# CaravanPi_V4.net
KiCad netlist of a schematic drawn in EAGLE
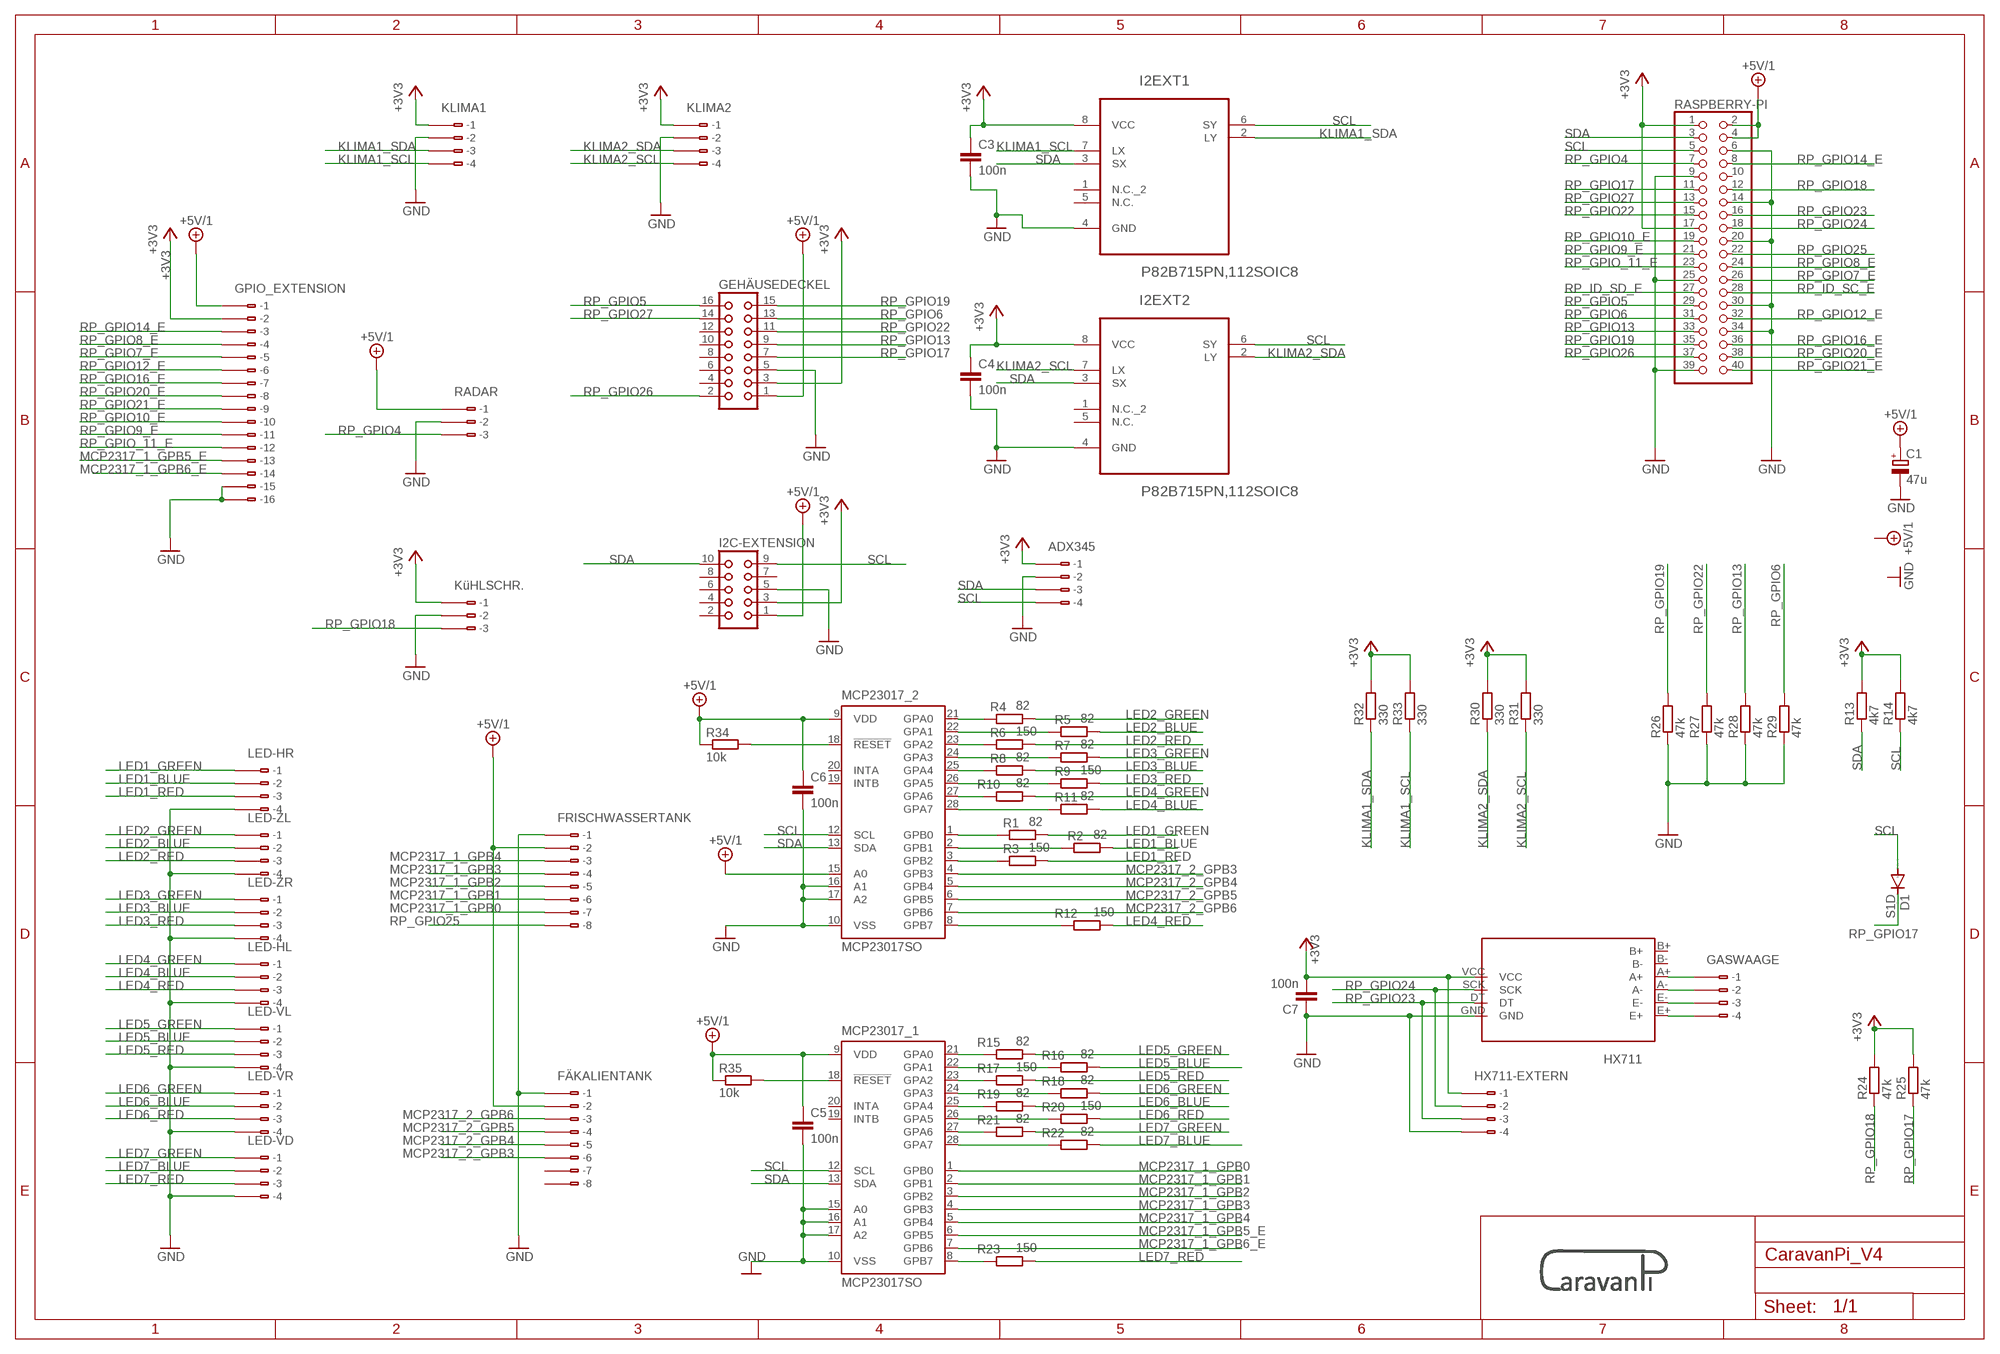
[diagram p0: schematic, sheet 1]

(export (version "E")
  (design (tool "Eeschema 10.0.6"))
  (components
    (comp (ref "ADX345")
      (value "233-404")
      (footprint "eagle-import:233-404")
      (libsource (lib "eagle-import") (part "233-404"))
    )
    (comp (ref "C1")
      (value "47u")
      (footprint "eagle-import:SMC_C")
      (libsource (lib "eagle-import") (part "CPOL-EUSMCC"))
    )
    (comp (ref "C3")
      (value "100n")
      (footprint "eagle-import:C1206")
      (libsource (lib "eagle-import") (part "C-EUC1206"))
    )
    (comp (ref "C4")
      (value "100n")
      (footprint "eagle-import:C1206")
      (libsource (lib "eagle-import") (part "C-EUC1206"))
    )
    (comp (ref "C5")
      (value "100n")
      (footprint "eagle-import:C1206")
      (libsource (lib "eagle-import") (part "C-EUC1206"))
    )
    (comp (ref "C6")
      (value "100n")
      (footprint "eagle-import:C1206")
      (libsource (lib "eagle-import") (part "C-EUC1206"))
    )
    (comp (ref "C7")
      (value "100n")
      (footprint "eagle-import:C1206")
      (libsource (lib "eagle-import") (part "C-EUC1206"))
    )
    (comp (ref "D1")
      (value "S1D")
      (footprint "eagle-import:DO214AC")
      (libsource (lib "eagle-import") (part "DIODE-DO214AC"))
    )
    (comp (ref "FRISCHWASSERTANK")
      (value "233-408")
      (footprint "eagle-import:233-408")
      (libsource (lib "eagle-import") (part "233-408"))
    )
    (comp (ref "FÄKALIENTANK")
      (value "233-408")
      (footprint "eagle-import:233-408")
      (libsource (lib "eagle-import") (part "233-408"))
    )
    (comp (ref "GASWAAGE")
      (value "233-404")
      (footprint "eagle-import:233-404")
      (libsource (lib "eagle-import") (part "233-404"))
    )
    (comp (ref "GEHÄUSEDECKEL")
      (value "CON16")
      (footprint "eagle-import:CON16")
      (libsource (lib "eagle-import") (part "CON16"))
    )
    (comp (ref "GPIO_EXTENSION")
      (value "233-516")
      (footprint "eagle-import:233-516")
      (fields (field (name "MF") "Wago Corporation") (field (name "MPN") "0233-0516"))
      (libsource (lib "eagle-import") (part "233-516"))
    )
    (comp (ref "HX711")
      (value "HX711A")
      (footprint "eagle-import:HX711")
      (libsource (lib "eagle-import") (part "HX711A"))
    )
    (comp (ref "HX711-EXTERN")
      (value "233-404")
      (footprint "eagle-import:233-404")
      (libsource (lib "eagle-import") (part "233-404"))
    )
    (comp (ref "I2C-EXTENSION")
      (value "CON10")
      (footprint "eagle-import:CON10")
      (libsource (lib "eagle-import") (part "CON10"))
    )
    (comp (ref "I2EXT1")
      (value "P82B715PN,112SOIC8")
      (footprint "eagle-import:SOP127P600X175-8N")
      (libsource (lib "eagle-import") (part "P82B715PN,112SOIC8"))
    )
    (comp (ref "I2EXT2")
      (value "P82B715PN,112SOIC8")
      (footprint "eagle-import:SOP127P600X175-8N")
      (libsource (lib "eagle-import") (part "P82B715PN,112SOIC8"))
    )
    (comp (ref "KLIMA1")
      (value "233-404")
      (footprint "eagle-import:233-404")
      (libsource (lib "eagle-import") (part "233-404"))
    )
    (comp (ref "KLIMA2")
      (value "233-404")
      (footprint "eagle-import:233-404")
      (libsource (lib "eagle-import") (part "233-404"))
    )
    (comp (ref "KüHLSCHR.")
      (value "233-403")
      (footprint "eagle-import:233-403")
      (libsource (lib "eagle-import") (part "233-403"))
    )
    (comp (ref "LED-HL")
      (value "233-504")
      (footprint "eagle-import:233-504")
      (fields (field (name "MF") "Wago Corporation") (field (name "MPN") "0233-0504"))
      (libsource (lib "eagle-import") (part "233-504"))
    )
    (comp (ref "LED-HR")
      (value "233-504")
      (footprint "eagle-import:233-504")
      (fields (field (name "MF") "Wago Corporation") (field (name "MPN") "0233-0504"))
      (libsource (lib "eagle-import") (part "233-504"))
    )
    (comp (ref "LED-VD")
      (value "233-504")
      (footprint "eagle-import:233-504")
      (fields (field (name "MF") "Wago Corporation") (field (name "MPN") "0233-0504"))
      (libsource (lib "eagle-import") (part "233-504"))
    )
    (comp (ref "LED-VL")
      (value "233-504")
      (footprint "eagle-import:233-504")
      (fields (field (name "MF") "Wago Corporation") (field (name "MPN") "0233-0504"))
      (libsource (lib "eagle-import") (part "233-504"))
    )
    (comp (ref "LED-VR")
      (value "233-504")
      (footprint "eagle-import:233-504")
      (fields (field (name "MF") "Wago Corporation") (field (name "MPN") "0233-0504"))
      (libsource (lib "eagle-import") (part "233-504"))
    )
    (comp (ref "LED-ZL")
      (value "233-504")
      (footprint "eagle-import:233-504")
      (fields (field (name "MF") "Wago Corporation") (field (name "MPN") "0233-0504"))
      (libsource (lib "eagle-import") (part "233-504"))
    )
    (comp (ref "LED-ZR")
      (value "233-504")
      (footprint "eagle-import:233-504")
      (fields (field (name "MF") "Wago Corporation") (field (name "MPN") "0233-0504"))
      (libsource (lib "eagle-import") (part "233-504"))
    )
    (comp (ref "MCP23017_1")
      (value "MCP23017SO")
      (footprint "eagle-import:SO28W")
      (libsource (lib "eagle-import") (part "MCP23017SO"))
    )
    (comp (ref "MCP23017_2")
      (value "MCP23017SO")
      (footprint "eagle-import:SO28W")
      (libsource (lib "eagle-import") (part "MCP23017SO"))
    )
    (comp (ref "R1")
      (value "82")
      (footprint "eagle-import:M1206")
      (libsource (lib "eagle-import") (part "R-EU_M1206"))
    )
    (comp (ref "R2")
      (value "82")
      (footprint "eagle-import:M1206")
      (libsource (lib "eagle-import") (part "R-EU_M1206"))
    )
    (comp (ref "R3")
      (value "150")
      (footprint "eagle-import:M1206")
      (libsource (lib "eagle-import") (part "R-EU_M1206"))
    )
    (comp (ref "R4")
      (value "82")
      (footprint "eagle-import:M1206")
      (libsource (lib "eagle-import") (part "R-EU_M1206"))
    )
    (comp (ref "R5")
      (value "82")
      (footprint "eagle-import:M1206")
      (libsource (lib "eagle-import") (part "R-EU_M1206"))
    )
    (comp (ref "R6")
      (value "150")
      (footprint "eagle-import:M1206")
      (libsource (lib "eagle-import") (part "R-EU_M1206"))
    )
    (comp (ref "R7")
      (value "82")
      (footprint "eagle-import:M1206")
      (libsource (lib "eagle-import") (part "R-EU_M1206"))
    )
    (comp (ref "R8")
      (value "82")
      (footprint "eagle-import:M1206")
      (libsource (lib "eagle-import") (part "R-EU_M1206"))
    )
    (comp (ref "R9")
      (value "150")
      (footprint "eagle-import:M1206")
      (libsource (lib "eagle-import") (part "R-EU_M1206"))
    )
    (comp (ref "R10")
      (value "82")
      (footprint "eagle-import:M1206")
      (libsource (lib "eagle-import") (part "R-EU_M1206"))
    )
    (comp (ref "R11")
      (value "82")
      (footprint "eagle-import:M1206")
      (libsource (lib "eagle-import") (part "R-EU_M1206"))
    )
    (comp (ref "R12")
      (value "150")
      (footprint "eagle-import:M1206")
      (libsource (lib "eagle-import") (part "R-EU_M1206"))
    )
    (comp (ref "R13")
      (value "4k7")
      (footprint "eagle-import:M1206")
      (libsource (lib "eagle-import") (part "R-EU_M1206"))
    )
    (comp (ref "R14")
      (value "4k7")
      (footprint "eagle-import:M1206")
      (libsource (lib "eagle-import") (part "R-EU_M1206"))
    )
    (comp (ref "R15")
      (value "82")
      (footprint "eagle-import:M1206")
      (libsource (lib "eagle-import") (part "R-EU_M1206"))
    )
    (comp (ref "R16")
      (value "82")
      (footprint "eagle-import:M1206")
      (libsource (lib "eagle-import") (part "R-EU_M1206"))
    )
    (comp (ref "R17")
      (value "150")
      (footprint "eagle-import:M1206")
      (libsource (lib "eagle-import") (part "R-EU_M1206"))
    )
    (comp (ref "R18")
      (value "82")
      (footprint "eagle-import:M1206")
      (libsource (lib "eagle-import") (part "R-EU_M1206"))
    )
    (comp (ref "R19")
      (value "82")
      (footprint "eagle-import:M1206")
      (libsource (lib "eagle-import") (part "R-EU_M1206"))
    )
    (comp (ref "R20")
      (value "150")
      (footprint "eagle-import:M1206")
      (libsource (lib "eagle-import") (part "R-EU_M1206"))
    )
    (comp (ref "R21")
      (value "82")
      (footprint "eagle-import:M1206")
      (libsource (lib "eagle-import") (part "R-EU_M1206"))
    )
    (comp (ref "R22")
      (value "82")
      (footprint "eagle-import:M1206")
      (libsource (lib "eagle-import") (part "R-EU_M1206"))
    )
    (comp (ref "R23")
      (value "150")
      (footprint "eagle-import:M1206")
      (libsource (lib "eagle-import") (part "R-EU_M1206"))
    )
    (comp (ref "R24")
      (value "47k")
      (footprint "eagle-import:M1206")
      (libsource (lib "eagle-import") (part "R-EU_M1206"))
    )
    (comp (ref "R25")
      (value "47k")
      (footprint "eagle-import:M1206")
      (libsource (lib "eagle-import") (part "R-EU_M1206"))
    )
    (comp (ref "R26")
      (value "47k")
      (footprint "eagle-import:M1206")
      (libsource (lib "eagle-import") (part "R-EU_M1206"))
    )
    (comp (ref "R27")
      (value "47k")
      (footprint "eagle-import:M1206")
      (libsource (lib "eagle-import") (part "R-EU_M1206"))
    )
    (comp (ref "R28")
      (value "47k")
      (footprint "eagle-import:M1206")
      (libsource (lib "eagle-import") (part "R-EU_M1206"))
    )
    (comp (ref "R29")
      (value "47k")
      (footprint "eagle-import:M1206")
      (libsource (lib "eagle-import") (part "R-EU_M1206"))
    )
    (comp (ref "R30")
      (value "330")
      (footprint "eagle-import:M1206")
      (libsource (lib "eagle-import") (part "R-EU_M1206"))
    )
    (comp (ref "R31")
      (value "330")
      (footprint "eagle-import:M1206")
      (libsource (lib "eagle-import") (part "R-EU_M1206"))
    )
    (comp (ref "R32")
      (value "330")
      (footprint "eagle-import:M1206")
      (libsource (lib "eagle-import") (part "R-EU_M1206"))
    )
    (comp (ref "R33")
      (value "330")
      (footprint "eagle-import:M1206")
      (libsource (lib "eagle-import") (part "R-EU_M1206"))
    )
    (comp (ref "R34")
      (value "10k")
      (footprint "eagle-import:M1206")
      (libsource (lib "eagle-import") (part "R-EU_M1206"))
    )
    (comp (ref "R35")
      (value "10k")
      (footprint "eagle-import:M1206")
      (libsource (lib "eagle-import") (part "R-EU_M1206"))
    )
    (comp (ref "RADAR")
      (value "233-403")
      (footprint "eagle-import:233-403")
      (libsource (lib "eagle-import") (part "233-403"))
    )
    (comp (ref "RASPBERRY-PI")
      (value "PINHD-2X20")
      (footprint "eagle-import:2X20")
      (libsource (lib "eagle-import") (part "PINHD-2X20"))
    )
    (comp (ref "U$1")
      (value "CARAVAN_PI_LOGO")
      (footprint "eagle-import:CARAVAN_PI_LOGO")
      (libsource (lib "eagle-import") (part "CARAVAN_PI_LOGO"))
    )
  )
  (nets
    (net (code "1") (name "+3V3") (class "Default")
      (node (ref "ADX345") (pin "B1") (pinfunction "B-1_B1") (pintype "passive"))
      (node (ref "C3") (pin "1") (pinfunction "1_1") (pintype "passive"))
      (node (ref "C4") (pin "1") (pinfunction "1_1") (pintype "passive"))
      (node (ref "C7") (pin "2") (pinfunction "2_2") (pintype "passive"))
      (node (ref "GEHÄUSEDECKEL") (pin "3") (pinfunction "3_3") (pintype "passive"))
      (node (ref "GPIO_EXTENSION") (pin "B2") (pinfunction "B-2_B2") (pintype "passive"))
      (node (ref "HX711") (pin "VCC") (pinfunction "VCC_VCC") (pintype "bidirectional"))
      (node (ref "HX711-EXTERN") (pin "B1") (pinfunction "B-1_B1") (pintype "passive"))
      (node (ref "I2C-EXTENSION") (pin "3") (pinfunction "3_3") (pintype "passive"))
      (node (ref "I2EXT1") (pin "8") (pinfunction "VCC_8") (pintype "power_in"))
      (node (ref "I2EXT2") (pin "8") (pinfunction "VCC_8") (pintype "power_in"))
      (node (ref "KLIMA1") (pin "B1") (pinfunction "B-1_B1") (pintype "passive"))
      (node (ref "KLIMA2") (pin "B1") (pinfunction "B-1_B1") (pintype "passive"))
      (node (ref "KüHLSCHR.") (pin "B1") (pinfunction "B-1_B1") (pintype "passive"))
      (node (ref "R13") (pin "2") (pinfunction "2_2") (pintype "passive"))
      (node (ref "R14") (pin "2") (pinfunction "2_2") (pintype "passive"))
      (node (ref "R24") (pin "2") (pinfunction "2_2") (pintype "passive"))
      (node (ref "R25") (pin "2") (pinfunction "2_2") (pintype "passive"))
      (node (ref "R30") (pin "2") (pinfunction "2_2") (pintype "passive"))
      (node (ref "R31") (pin "2") (pinfunction "2_2") (pintype "passive"))
      (node (ref "R32") (pin "2") (pinfunction "2_2") (pintype "passive"))
      (node (ref "R33") (pin "2") (pinfunction "2_2") (pintype "passive"))
      (node (ref "RASPBERRY-PI") (pin "1") (pinfunction "1_1") (pintype "passive"))
      (node (ref "RASPBERRY-PI") (pin "17") (pinfunction "17_17") (pintype "passive"))
    )
    (net (code "2") (name "+5V{slash}1") (class "Default")
      (node (ref "C1") (pin "+") (pinfunction "+_+") (pintype "passive"))
      (node (ref "C5") (pin "1") (pinfunction "1_1") (pintype "passive"))
      (node (ref "C6") (pin "1") (pinfunction "1_1") (pintype "passive"))
      (node (ref "FRISCHWASSERTANK") (pin "B2") (pinfunction "B-2_B2") (pintype "passive"))
      (node (ref "FÄKALIENTANK") (pin "B2") (pinfunction "B-2_B2") (pintype "passive"))
      (node (ref "GEHÄUSEDECKEL") (pin "1") (pinfunction "1_1") (pintype "passive"))
      (node (ref "GPIO_EXTENSION") (pin "B1") (pinfunction "B-1_B1") (pintype "passive"))
      (node (ref "I2C-EXTENSION") (pin "1") (pinfunction "1_1") (pintype "passive"))
      (node (ref "MCP23017_1") (pin "9") (pinfunction "VDD_9") (pintype "power_in"))
      (node (ref "MCP23017_2") (pin "15") (pinfunction "A0_15") (pintype "input"))
      (node (ref "MCP23017_2") (pin "9") (pinfunction "VDD_9") (pintype "power_in"))
      (node (ref "R34") (pin "1") (pinfunction "1_1") (pintype "passive"))
      (node (ref "R35") (pin "1") (pinfunction "1_1") (pintype "passive"))
      (node (ref "RADAR") (pin "B1") (pinfunction "B-1_B1") (pintype "passive"))
      (node (ref "RASPBERRY-PI") (pin "2") (pinfunction "2_2") (pintype "passive"))
      (node (ref "RASPBERRY-PI") (pin "4") (pinfunction "4_4") (pintype "passive"))
    )
    (net (code "3") (name "/KLIMA1_SCL") (class "Default")
      (node (ref "I2EXT1") (pin "7") (pinfunction "LX_7") (pintype "bidirectional"))
      (node (ref "KLIMA1") (pin "B4") (pinfunction "B-4_B4") (pintype "passive"))
      (node (ref "R33") (pin "1") (pinfunction "1_1") (pintype "passive"))
    )
    (net (code "4") (name "/KLIMA1_SDA") (class "Default")
      (node (ref "I2EXT1") (pin "2") (pinfunction "LY_2") (pintype "bidirectional"))
      (node (ref "KLIMA1") (pin "B3") (pinfunction "B-3_B3") (pintype "passive"))
      (node (ref "R32") (pin "1") (pinfunction "1_1") (pintype "passive"))
    )
    (net (code "5") (name "/KLIMA2_SCL") (class "Default")
      (node (ref "I2EXT2") (pin "7") (pinfunction "LX_7") (pintype "bidirectional"))
      (node (ref "KLIMA2") (pin "B4") (pinfunction "B-4_B4") (pintype "passive"))
      (node (ref "R31") (pin "1") (pinfunction "1_1") (pintype "passive"))
    )
    (net (code "6") (name "/KLIMA2_SDA") (class "Default")
      (node (ref "I2EXT2") (pin "2") (pinfunction "LY_2") (pintype "bidirectional"))
      (node (ref "KLIMA2") (pin "B3") (pinfunction "B-3_B3") (pintype "passive"))
      (node (ref "R30") (pin "1") (pinfunction "1_1") (pintype "passive"))
    )
    (net (code "7") (name "/LED1_BLUE") (class "Default")
      (node (ref "LED-HR") (pin "B2") (pinfunction "B-2_B2") (pintype "passive"))
      (node (ref "R2") (pin "2") (pinfunction "2_2") (pintype "passive"))
    )
    (net (code "8") (name "/LED1_GREEN") (class "Default")
      (node (ref "LED-HR") (pin "B1") (pinfunction "B-1_B1") (pintype "passive"))
      (node (ref "R1") (pin "2") (pinfunction "2_2") (pintype "passive"))
    )
    (net (code "9") (name "/LED1_RED") (class "Default")
      (node (ref "LED-HR") (pin "B3") (pinfunction "B-3_B3") (pintype "passive"))
      (node (ref "R3") (pin "2") (pinfunction "2_2") (pintype "passive"))
    )
    (net (code "10") (name "/LED2_BLUE") (class "Default")
      (node (ref "LED-ZL") (pin "B2") (pinfunction "B-2_B2") (pintype "passive"))
      (node (ref "R5") (pin "2") (pinfunction "2_2") (pintype "passive"))
    )
    (net (code "11") (name "/LED2_GREEN") (class "Default")
      (node (ref "LED-ZL") (pin "B1") (pinfunction "B-1_B1") (pintype "passive"))
      (node (ref "R4") (pin "2") (pinfunction "2_2") (pintype "passive"))
    )
    (net (code "12") (name "/LED2_RED") (class "Default")
      (node (ref "LED-ZL") (pin "B3") (pinfunction "B-3_B3") (pintype "passive"))
      (node (ref "R6") (pin "2") (pinfunction "2_2") (pintype "passive"))
    )
    (net (code "13") (name "/LED3_BLUE") (class "Default")
      (node (ref "LED-ZR") (pin "B2") (pinfunction "B-2_B2") (pintype "passive"))
      (node (ref "R8") (pin "2") (pinfunction "2_2") (pintype "passive"))
    )
    (net (code "14") (name "/LED3_GREEN") (class "Default")
      (node (ref "LED-ZR") (pin "B1") (pinfunction "B-1_B1") (pintype "passive"))
      (node (ref "R7") (pin "2") (pinfunction "2_2") (pintype "passive"))
    )
    (net (code "15") (name "/LED3_RED") (class "Default")
      (node (ref "LED-ZR") (pin "B3") (pinfunction "B-3_B3") (pintype "passive"))
      (node (ref "R9") (pin "2") (pinfunction "2_2") (pintype "passive"))
    )
    (net (code "16") (name "/LED4_BLUE") (class "Default")
      (node (ref "LED-HL") (pin "B2") (pinfunction "B-2_B2") (pintype "passive"))
      (node (ref "R11") (pin "2") (pinfunction "2_2") (pintype "passive"))
    )
    (net (code "17") (name "/LED4_GREEN") (class "Default")
      (node (ref "LED-HL") (pin "B1") (pinfunction "B-1_B1") (pintype "passive"))
      (node (ref "R10") (pin "2") (pinfunction "2_2") (pintype "passive"))
    )
    (net (code "18") (name "/LED4_RED") (class "Default")
      (node (ref "LED-HL") (pin "B3") (pinfunction "B-3_B3") (pintype "passive"))
      (node (ref "R12") (pin "2") (pinfunction "2_2") (pintype "passive"))
    )
    (net (code "19") (name "/LED5_BLUE") (class "Default")
      (node (ref "LED-VL") (pin "B2") (pinfunction "B-2_B2") (pintype "passive"))
      (node (ref "R16") (pin "2") (pinfunction "2_2") (pintype "passive"))
    )
    (net (code "20") (name "/LED5_GREEN") (class "Default")
      (node (ref "LED-VL") (pin "B1") (pinfunction "B-1_B1") (pintype "passive"))
      (node (ref "R15") (pin "2") (pinfunction "2_2") (pintype "passive"))
    )
    (net (code "21") (name "/LED5_RED") (class "Default")
      (node (ref "LED-VL") (pin "B3") (pinfunction "B-3_B3") (pintype "passive"))
      (node (ref "R17") (pin "2") (pinfunction "2_2") (pintype "passive"))
    )
    (net (code "22") (name "/LED6_BLUE") (class "Default")
      (node (ref "LED-VR") (pin "B2") (pinfunction "B-2_B2") (pintype "passive"))
      (node (ref "R19") (pin "2") (pinfunction "2_2") (pintype "passive"))
    )
    (net (code "23") (name "/LED6_GREEN") (class "Default")
      (node (ref "LED-VR") (pin "B1") (pinfunction "B-1_B1") (pintype "passive"))
      (node (ref "R18") (pin "2") (pinfunction "2_2") (pintype "passive"))
    )
    (net (code "24") (name "/LED6_RED") (class "Default")
      (node (ref "LED-VR") (pin "B3") (pinfunction "B-3_B3") (pintype "passive"))
      (node (ref "R20") (pin "2") (pinfunction "2_2") (pintype "passive"))
    )
    (net (code "25") (name "/LED7_BLUE") (class "Default")
      (node (ref "LED-VD") (pin "B2") (pinfunction "B-2_B2") (pintype "passive"))
      (node (ref "R22") (pin "2") (pinfunction "2_2") (pintype "passive"))
    )
    (net (code "26") (name "/LED7_GREEN") (class "Default")
      (node (ref "LED-VD") (pin "B1") (pinfunction "B-1_B1") (pintype "passive"))
      (node (ref "R21") (pin "2") (pinfunction "2_2") (pintype "passive"))
    )
    (net (code "27") (name "/LED7_RED") (class "Default")
      (node (ref "LED-VD") (pin "B3") (pinfunction "B-3_B3") (pintype "passive"))
      (node (ref "R23") (pin "2") (pinfunction "2_2") (pintype "passive"))
    )
    (net (code "28") (name "/MCP2317_1_GPB0") (class "Default")
      (node (ref "FRISCHWASSERTANK") (pin "B7") (pinfunction "B-7_B7") (pintype "passive"))
      (node (ref "MCP23017_1") (pin "1") (pinfunction "GPB0_1") (pintype "bidirectional"))
    )
    (net (code "29") (name "/MCP2317_1_GPB1") (class "Default")
      (node (ref "FRISCHWASSERTANK") (pin "B6") (pinfunction "B-6_B6") (pintype "passive"))
      (node (ref "MCP23017_1") (pin "2") (pinfunction "GPB1_2") (pintype "bidirectional"))
    )
    (net (code "30") (name "/MCP2317_1_GPB2") (class "Default")
      (node (ref "FRISCHWASSERTANK") (pin "B5") (pinfunction "B-5_B5") (pintype "passive"))
      (node (ref "MCP23017_1") (pin "3") (pinfunction "GPB2_3") (pintype "bidirectional"))
    )
    (net (code "31") (name "/MCP2317_1_GPB3") (class "Default")
      (node (ref "FRISCHWASSERTANK") (pin "B4") (pinfunction "B-4_B4") (pintype "passive"))
      (node (ref "MCP23017_1") (pin "4") (pinfunction "GPB3_4") (pintype "bidirectional"))
    )
    (net (code "32") (name "/MCP2317_1_GPB4") (class "Default")
      (node (ref "FRISCHWASSERTANK") (pin "B3") (pinfunction "B-3_B3") (pintype "passive"))
      (node (ref "MCP23017_1") (pin "5") (pinfunction "GPB4_5") (pintype "bidirectional"))
    )
    (net (code "33") (name "/MCP2317_1_GPB5_E") (class "Default")
      (node (ref "GPIO_EXTENSION") (pin "B13") (pinfunction "B-13_B13") (pintype "passive"))
      (node (ref "MCP23017_1") (pin "6") (pinfunction "GPB5_6") (pintype "bidirectional"))
    )
    (net (code "34") (name "/MCP2317_1_GPB6_E") (class "Default")
      (node (ref "GPIO_EXTENSION") (pin "B14") (pinfunction "B-14_B14") (pintype "passive"))
      (node (ref "MCP23017_1") (pin "7") (pinfunction "GPB6_7") (pintype "bidirectional"))
    )
    (net (code "35") (name "/MCP2317_2_GPB3") (class "Default")
      (node (ref "FÄKALIENTANK") (pin "B6") (pinfunction "B-6_B6") (pintype "passive"))
      (node (ref "MCP23017_2") (pin "4") (pinfunction "GPB3_4") (pintype "bidirectional"))
    )
    (net (code "36") (name "/MCP2317_2_GPB4") (class "Default")
      (node (ref "FÄKALIENTANK") (pin "B5") (pinfunction "B-5_B5") (pintype "passive"))
      (node (ref "MCP23017_2") (pin "5") (pinfunction "GPB4_5") (pintype "bidirectional"))
    )
    (net (code "37") (name "/MCP2317_2_GPB5") (class "Default")
      (node (ref "FÄKALIENTANK") (pin "B4") (pinfunction "B-4_B4") (pintype "passive"))
      (node (ref "MCP23017_2") (pin "6") (pinfunction "GPB5_6") (pintype "bidirectional"))
    )
    (net (code "38") (name "/MCP2317_2_GPB6") (class "Default")
      (node (ref "FÄKALIENTANK") (pin "B3") (pinfunction "B-3_B3") (pintype "passive"))
      (node (ref "MCP23017_2") (pin "7") (pinfunction "GPB6_7") (pintype "bidirectional"))
    )
    (net (code "39") (name "/RP_GPIO4") (class "Default")
      (node (ref "RADAR") (pin "B3") (pinfunction "B-3_B3") (pintype "passive"))
      (node (ref "RASPBERRY-PI") (pin "7") (pinfunction "7_7") (pintype "passive"))
    )
    (net (code "40") (name "/RP_GPIO5") (class "Default")
      (node (ref "GEHÄUSEDECKEL") (pin "16") (pinfunction "16_16") (pintype "passive"))
      (node (ref "RASPBERRY-PI") (pin "29") (pinfunction "29_29") (pintype "passive"))
    )
    (net (code "41") (name "/RP_GPIO6") (class "Default")
      (node (ref "GEHÄUSEDECKEL") (pin "13") (pinfunction "13_13") (pintype "passive"))
      (node (ref "R29") (pin "2") (pinfunction "2_2") (pintype "passive"))
      (node (ref "RASPBERRY-PI") (pin "31") (pinfunction "31_31") (pintype "passive"))
    )
    (net (code "42") (name "/RP_GPIO7_E") (class "Default")
      (node (ref "GPIO_EXTENSION") (pin "B5") (pinfunction "B-5_B5") (pintype "passive"))
      (node (ref "RASPBERRY-PI") (pin "26") (pinfunction "26_26") (pintype "passive"))
    )
    (net (code "43") (name "/RP_GPIO8_E") (class "Default")
      (node (ref "GPIO_EXTENSION") (pin "B4") (pinfunction "B-4_B4") (pintype "passive"))
      (node (ref "RASPBERRY-PI") (pin "24") (pinfunction "24_24") (pintype "passive"))
    )
    (net (code "44") (name "/RP_GPIO9_E") (class "Default")
      (node (ref "GPIO_EXTENSION") (pin "B11") (pinfunction "B-11_B11") (pintype "passive"))
      (node (ref "RASPBERRY-PI") (pin "21") (pinfunction "21_21") (pintype "passive"))
    )
    (net (code "45") (name "/RP_GPIO10_E") (class "Default")
      (node (ref "GPIO_EXTENSION") (pin "B10") (pinfunction "B-10_B10") (pintype "passive"))
      (node (ref "RASPBERRY-PI") (pin "19") (pinfunction "19_19") (pintype "passive"))
    )
    (net (code "46") (name "/RP_GPIO12_E") (class "Default")
      (node (ref "GPIO_EXTENSION") (pin "B6") (pinfunction "B-6_B6") (pintype "passive"))
      (node (ref "RASPBERRY-PI") (pin "32") (pinfunction "32_32") (pintype "passive"))
    )
    (net (code "47") (name "/RP_GPIO13") (class "Default")
      (node (ref "GEHÄUSEDECKEL") (pin "9") (pinfunction "9_9") (pintype "passive"))
      (node (ref "R28") (pin "2") (pinfunction "2_2") (pintype "passive"))
      (node (ref "RASPBERRY-PI") (pin "33") (pinfunction "33_33") (pintype "passive"))
    )
    (net (code "48") (name "/RP_GPIO14_E") (class "Default")
      (node (ref "GPIO_EXTENSION") (pin "B3") (pinfunction "B-3_B3") (pintype "passive"))
      (node (ref "RASPBERRY-PI") (pin "8") (pinfunction "8_8") (pintype "passive"))
    )
    (net (code "49") (name "/RP_GPIO16_E") (class "Default")
      (node (ref "GPIO_EXTENSION") (pin "B7") (pinfunction "B-7_B7") (pintype "passive"))
      (node (ref "RASPBERRY-PI") (pin "36") (pinfunction "36_36") (pintype "passive"))
    )
    (net (code "50") (name "/RP_GPIO17") (class "Default")
      (node (ref "D1") (pin "C") (pinfunction "C_C") (pintype "passive"))
      (node (ref "GEHÄUSEDECKEL") (pin "7") (pinfunction "7_7") (pintype "passive"))
      (node (ref "R25") (pin "1") (pinfunction "1_1") (pintype "passive"))
      (node (ref "RASPBERRY-PI") (pin "11") (pinfunction "11_11") (pintype "passive"))
    )
    (net (code "51") (name "/RP_GPIO18") (class "Default")
      (node (ref "KüHLSCHR.") (pin "B3") (pinfunction "B-3_B3") (pintype "passive"))
      (node (ref "R24") (pin "1") (pinfunction "1_1") (pintype "passive"))
      (node (ref "RASPBERRY-PI") (pin "12") (pinfunction "12_12") (pintype "passive"))
    )
    (net (code "52") (name "/RP_GPIO19") (class "Default")
      (node (ref "GEHÄUSEDECKEL") (pin "15") (pinfunction "15_15") (pintype "passive"))
      (node (ref "R26") (pin "2") (pinfunction "2_2") (pintype "passive"))
      (node (ref "RASPBERRY-PI") (pin "35") (pinfunction "35_35") (pintype "passive"))
    )
    (net (code "53") (name "/RP_GPIO20_E") (class "Default")
      (node (ref "GPIO_EXTENSION") (pin "B8") (pinfunction "B-8_B8") (pintype "passive"))
      (node (ref "RASPBERRY-PI") (pin "38") (pinfunction "38_38") (pintype "passive"))
    )
    (net (code "54") (name "/RP_GPIO21_E") (class "Default")
      (node (ref "GPIO_EXTENSION") (pin "B9") (pinfunction "B-9_B9") (pintype "passive"))
      (node (ref "RASPBERRY-PI") (pin "40") (pinfunction "40_40") (pintype "passive"))
    )
    (net (code "55") (name "/RP_GPIO22") (class "Default")
      (node (ref "GEHÄUSEDECKEL") (pin "11") (pinfunction "11_11") (pintype "passive"))
      (node (ref "R27") (pin "2") (pinfunction "2_2") (pintype "passive"))
      (node (ref "RASPBERRY-PI") (pin "15") (pinfunction "15_15") (pintype "passive"))
    )
    (net (code "56") (name "/RP_GPIO23") (class "Default")
      (node (ref "HX711") (pin "DT") (pinfunction "DT_DT") (pintype "bidirectional"))
      (node (ref "HX711-EXTERN") (pin "B3") (pinfunction "B-3_B3") (pintype "passive"))
      (node (ref "RASPBERRY-PI") (pin "16") (pinfunction "16_16") (pintype "passive"))
    )
    (net (code "57") (name "/RP_GPIO24") (class "Default")
      (node (ref "HX711") (pin "SCK") (pinfunction "SCK_SCK") (pintype "bidirectional"))
      (node (ref "HX711-EXTERN") (pin "B2") (pinfunction "B-2_B2") (pintype "passive"))
      (node (ref "RASPBERRY-PI") (pin "18") (pinfunction "18_18") (pintype "passive"))
    )
    (net (code "58") (name "/RP_GPIO25") (class "Default")
      (node (ref "FRISCHWASSERTANK") (pin "B8") (pinfunction "B-8_B8") (pintype "passive"))
      (node (ref "RASPBERRY-PI") (pin "22") (pinfunction "22_22") (pintype "passive"))
    )
    (net (code "59") (name "/RP_GPIO26") (class "Default")
      (node (ref "GEHÄUSEDECKEL") (pin "2") (pinfunction "2_2") (pintype "passive"))
      (node (ref "RASPBERRY-PI") (pin "37") (pinfunction "37_37") (pintype "passive"))
    )
    (net (code "60") (name "/RP_GPIO27") (class "Default")
      (node (ref "GEHÄUSEDECKEL") (pin "14") (pinfunction "14_14") (pintype "passive"))
      (node (ref "RASPBERRY-PI") (pin "13") (pinfunction "13_13") (pintype "passive"))
    )
    (net (code "61") (name "/RP_GPIO_11_E") (class "Default")
      (node (ref "GPIO_EXTENSION") (pin "B12") (pinfunction "B-12_B12") (pintype "passive"))
      (node (ref "RASPBERRY-PI") (pin "23") (pinfunction "23_23") (pintype "passive"))
    )
    (net (code "62") (name "/RP_ID_SC_E") (class "Default")
      (node (ref "RASPBERRY-PI") (pin "28") (pinfunction "28_28") (pintype "passive"))
    )
    (net (code "63") (name "/RP_ID_SD_E") (class "Default")
      (node (ref "RASPBERRY-PI") (pin "27") (pinfunction "27_27") (pintype "passive"))
    )
    (net (code "64") (name "/SCL") (class "Default")
      (node (ref "ADX345") (pin "B4") (pinfunction "B-4_B4") (pintype "passive"))
      (node (ref "D1") (pin "A") (pinfunction "A_A") (pintype "passive"))
      (node (ref "I2C-EXTENSION") (pin "9") (pinfunction "9_9") (pintype "passive"))
      (node (ref "I2EXT1") (pin "6") (pinfunction "SY_6") (pintype "bidirectional"))
      (node (ref "I2EXT2") (pin "6") (pinfunction "SY_6") (pintype "bidirectional"))
      (node (ref "MCP23017_1") (pin "12") (pinfunction "SCL_12") (pintype "input"))
      (node (ref "MCP23017_2") (pin "12") (pinfunction "SCL_12") (pintype "input"))
      (node (ref "R14") (pin "1") (pinfunction "1_1") (pintype "passive"))
      (node (ref "RASPBERRY-PI") (pin "5") (pinfunction "5_5") (pintype "passive"))
    )
    (net (code "65") (name "/SDA") (class "Default")
      (node (ref "ADX345") (pin "B3") (pinfunction "B-3_B3") (pintype "passive"))
      (node (ref "I2C-EXTENSION") (pin "10") (pinfunction "10_10") (pintype "passive"))
      (node (ref "I2EXT1") (pin "3") (pinfunction "SX_3") (pintype "bidirectional"))
      (node (ref "I2EXT2") (pin "3") (pinfunction "SX_3") (pintype "bidirectional"))
      (node (ref "MCP23017_1") (pin "13") (pinfunction "SDA_13") (pintype "bidirectional"))
      (node (ref "MCP23017_2") (pin "13") (pinfunction "SDA_13") (pintype "bidirectional"))
      (node (ref "R13") (pin "1") (pinfunction "1_1") (pintype "passive"))
      (node (ref "RASPBERRY-PI") (pin "3") (pinfunction "3_3") (pintype "passive"))
    )
    (net (code "66") (name "GND") (class "Default")
      (node (ref "ADX345") (pin "B2") (pinfunction "B-2_B2") (pintype "passive"))
      (node (ref "C1") (pin "-") (pinfunction "-_-") (pintype "passive"))
      (node (ref "C3") (pin "2") (pinfunction "2_2") (pintype "passive"))
      (node (ref "C4") (pin "2") (pinfunction "2_2") (pintype "passive"))
      (node (ref "C5") (pin "2") (pinfunction "2_2") (pintype "passive"))
      (node (ref "C6") (pin "2") (pinfunction "2_2") (pintype "passive"))
      (node (ref "C7") (pin "1") (pinfunction "1_1") (pintype "passive"))
      (node (ref "FRISCHWASSERTANK") (pin "B1") (pinfunction "B-1_B1") (pintype "passive"))
      (node (ref "FÄKALIENTANK") (pin "B1") (pinfunction "B-1_B1") (pintype "passive"))
      (node (ref "GEHÄUSEDECKEL") (pin "5") (pinfunction "5_5") (pintype "passive"))
      (node (ref "GPIO_EXTENSION") (pin "B15") (pinfunction "B-15_B15") (pintype "passive"))
      (node (ref "GPIO_EXTENSION") (pin "B16") (pinfunction "B-16_B16") (pintype "passive"))
      (node (ref "HX711") (pin "GND") (pinfunction "GND_GND") (pintype "bidirectional"))
      (node (ref "HX711-EXTERN") (pin "B4") (pinfunction "B-4_B4") (pintype "passive"))
      (node (ref "I2C-EXTENSION") (pin "5") (pinfunction "5_5") (pintype "passive"))
      (node (ref "I2EXT1") (pin "4") (pinfunction "GND_4") (pintype "passive"))
      (node (ref "I2EXT2") (pin "4") (pinfunction "GND_4") (pintype "passive"))
      (node (ref "KLIMA1") (pin "B2") (pinfunction "B-2_B2") (pintype "passive"))
      (node (ref "KLIMA2") (pin "B2") (pinfunction "B-2_B2") (pintype "passive"))
      (node (ref "KüHLSCHR.") (pin "B2") (pinfunction "B-2_B2") (pintype "passive"))
      (node (ref "LED-HL") (pin "B4") (pinfunction "B-4_B4") (pintype "passive"))
      (node (ref "LED-HR") (pin "B4") (pinfunction "B-4_B4") (pintype "passive"))
      (node (ref "LED-VD") (pin "B4") (pinfunction "B-4_B4") (pintype "passive"))
      (node (ref "LED-VL") (pin "B4") (pinfunction "B-4_B4") (pintype "passive"))
      (node (ref "LED-VR") (pin "B4") (pinfunction "B-4_B4") (pintype "passive"))
      (node (ref "LED-ZL") (pin "B4") (pinfunction "B-4_B4") (pintype "passive"))
      (node (ref "LED-ZR") (pin "B4") (pinfunction "B-4_B4") (pintype "passive"))
      (node (ref "MCP23017_1") (pin "10") (pinfunction "VSS_10") (pintype "power_in"))
      (node (ref "MCP23017_1") (pin "15") (pinfunction "A0_15") (pintype "input"))
      (node (ref "MCP23017_1") (pin "16") (pinfunction "A1_16") (pintype "input"))
      (node (ref "MCP23017_1") (pin "17") (pinfunction "A2_17") (pintype "input"))
      (node (ref "MCP23017_2") (pin "10") (pinfunction "VSS_10") (pintype "power_in"))
      (node (ref "MCP23017_2") (pin "16") (pinfunction "A1_16") (pintype "input"))
      (node (ref "MCP23017_2") (pin "17") (pinfunction "A2_17") (pintype "input"))
      (node (ref "R26") (pin "1") (pinfunction "1_1") (pintype "passive"))
      (node (ref "R27") (pin "1") (pinfunction "1_1") (pintype "passive"))
      (node (ref "R28") (pin "1") (pinfunction "1_1") (pintype "passive"))
      (node (ref "R29") (pin "1") (pinfunction "1_1") (pintype "passive"))
      (node (ref "RADAR") (pin "B2") (pinfunction "B-2_B2") (pintype "passive"))
      (node (ref "RASPBERRY-PI") (pin "14") (pinfunction "14_14") (pintype "passive"))
      (node (ref "RASPBERRY-PI") (pin "20") (pinfunction "20_20") (pintype "passive"))
      (node (ref "RASPBERRY-PI") (pin "25") (pinfunction "25_25") (pintype "passive"))
      (node (ref "RASPBERRY-PI") (pin "30") (pinfunction "30_30") (pintype "passive"))
      (node (ref "RASPBERRY-PI") (pin "34") (pinfunction "34_34") (pintype "passive"))
      (node (ref "RASPBERRY-PI") (pin "39") (pinfunction "39_39") (pintype "passive"))
      (node (ref "RASPBERRY-PI") (pin "6") (pinfunction "6_6") (pintype "passive"))
      (node (ref "RASPBERRY-PI") (pin "9") (pinfunction "9_9") (pintype "passive"))
    )
    (net (code "67") (name "Net-(GASWAAGE-B-1)") (class "Default")
      (node (ref "GASWAAGE") (pin "B1") (pinfunction "B-1_B1") (pintype "passive"))
      (node (ref "HX711") (pin "A+") (pinfunction "A+_A+") (pintype "bidirectional"))
    )
    (net (code "68") (name "Net-(GASWAAGE-B-2)") (class "Default")
      (node (ref "GASWAAGE") (pin "B2") (pinfunction "B-2_B2") (pintype "passive"))
      (node (ref "HX711") (pin "A-") (pinfunction "A-_A-") (pintype "bidirectional"))
    )
    (net (code "69") (name "Net-(GASWAAGE-B-3)") (class "Default")
      (node (ref "GASWAAGE") (pin "B3") (pinfunction "B-3_B3") (pintype "passive"))
      (node (ref "HX711") (pin "E-") (pinfunction "E-_E-") (pintype "bidirectional"))
    )
    (net (code "70") (name "Net-(GASWAAGE-B-4)") (class "Default")
      (node (ref "GASWAAGE") (pin "B4") (pinfunction "B-4_B4") (pintype "passive"))
      (node (ref "HX711") (pin "E+") (pinfunction "E+_E+") (pintype "bidirectional"))
    )
    (net (code "71") (name "Net-(MCP23017_1-GPA0)") (class "Default")
      (node (ref "MCP23017_1") (pin "21") (pinfunction "GPA0_21") (pintype "bidirectional"))
      (node (ref "R15") (pin "1") (pinfunction "1_1") (pintype "passive"))
    )
    (net (code "72") (name "Net-(MCP23017_1-GPA1)") (class "Default")
      (node (ref "MCP23017_1") (pin "22") (pinfunction "GPA1_22") (pintype "bidirectional"))
      (node (ref "R16") (pin "1") (pinfunction "1_1") (pintype "passive"))
    )
    (net (code "73") (name "Net-(MCP23017_1-GPA2)") (class "Default")
      (node (ref "MCP23017_1") (pin "23") (pinfunction "GPA2_23") (pintype "bidirectional"))
      (node (ref "R17") (pin "1") (pinfunction "1_1") (pintype "passive"))
    )
    (net (code "74") (name "Net-(MCP23017_1-GPA3)") (class "Default")
      (node (ref "MCP23017_1") (pin "24") (pinfunction "GPA3_24") (pintype "bidirectional"))
      (node (ref "R18") (pin "1") (pinfunction "1_1") (pintype "passive"))
    )
    (net (code "75") (name "Net-(MCP23017_1-GPA4)") (class "Default")
      (node (ref "MCP23017_1") (pin "25") (pinfunction "GPA4_25") (pintype "bidirectional"))
      (node (ref "R19") (pin "1") (pinfunction "1_1") (pintype "passive"))
    )
    (net (code "76") (name "Net-(MCP23017_1-GPA5)") (class "Default")
      (node (ref "MCP23017_1") (pin "26") (pinfunction "GPA5_26") (pintype "bidirectional"))
      (node (ref "R20") (pin "1") (pinfunction "1_1") (pintype "passive"))
    )
    (net (code "77") (name "Net-(MCP23017_1-GPA6)") (class "Default")
      (node (ref "MCP23017_1") (pin "27") (pinfunction "GPA6_27") (pintype "bidirectional"))
      (node (ref "R21") (pin "1") (pinfunction "1_1") (pintype "passive"))
    )
    (net (code "78") (name "Net-(MCP23017_1-GPA7)") (class "Default")
      (node (ref "MCP23017_1") (pin "28") (pinfunction "GPA7_28") (pintype "bidirectional"))
      (node (ref "R22") (pin "1") (pinfunction "1_1") (pintype "passive"))
    )
    (net (code "79") (name "Net-(MCP23017_1-GPB7)") (class "Default")
      (node (ref "MCP23017_1") (pin "8") (pinfunction "GPB7_8") (pintype "bidirectional"))
      (node (ref "R23") (pin "1") (pinfunction "1_1") (pintype "passive"))
    )
    (net (code "80") (name "Net-(MCP23017_1-~{RESET})") (class "Default")
      (node (ref "MCP23017_1") (pin "18") (pinfunction "~{RESET}_18") (pintype "input"))
      (node (ref "R35") (pin "2") (pinfunction "2_2") (pintype "passive"))
    )
    (net (code "81") (name "Net-(MCP23017_2-GPA0)") (class "Default")
      (node (ref "MCP23017_2") (pin "21") (pinfunction "GPA0_21") (pintype "bidirectional"))
      (node (ref "R4") (pin "1") (pinfunction "1_1") (pintype "passive"))
    )
    (net (code "82") (name "Net-(MCP23017_2-GPA1)") (class "Default")
      (node (ref "MCP23017_2") (pin "22") (pinfunction "GPA1_22") (pintype "bidirectional"))
      (node (ref "R5") (pin "1") (pinfunction "1_1") (pintype "passive"))
    )
    (net (code "83") (name "Net-(MCP23017_2-GPA2)") (class "Default")
      (node (ref "MCP23017_2") (pin "23") (pinfunction "GPA2_23") (pintype "bidirectional"))
      (node (ref "R6") (pin "1") (pinfunction "1_1") (pintype "passive"))
    )
    (net (code "84") (name "Net-(MCP23017_2-GPA3)") (class "Default")
      (node (ref "MCP23017_2") (pin "24") (pinfunction "GPA3_24") (pintype "bidirectional"))
      (node (ref "R7") (pin "1") (pinfunction "1_1") (pintype "passive"))
    )
    (net (code "85") (name "Net-(MCP23017_2-GPA4)") (class "Default")
      (node (ref "MCP23017_2") (pin "25") (pinfunction "GPA4_25") (pintype "bidirectional"))
      (node (ref "R8") (pin "1") (pinfunction "1_1") (pintype "passive"))
    )
    (net (code "86") (name "Net-(MCP23017_2-GPA5)") (class "Default")
      (node (ref "MCP23017_2") (pin "26") (pinfunction "GPA5_26") (pintype "bidirectional"))
      (node (ref "R9") (pin "1") (pinfunction "1_1") (pintype "passive"))
    )
    (net (code "87") (name "Net-(MCP23017_2-GPA6)") (class "Default")
      (node (ref "MCP23017_2") (pin "27") (pinfunction "GPA6_27") (pintype "bidirectional"))
      (node (ref "R10") (pin "1") (pinfunction "1_1") (pintype "passive"))
    )
    (net (code "88") (name "Net-(MCP23017_2-GPA7)") (class "Default")
      (node (ref "MCP23017_2") (pin "28") (pinfunction "GPA7_28") (pintype "bidirectional"))
      (node (ref "R11") (pin "1") (pinfunction "1_1") (pintype "passive"))
    )
    (net (code "89") (name "Net-(MCP23017_2-GPB0)") (class "Default")
      (node (ref "MCP23017_2") (pin "1") (pinfunction "GPB0_1") (pintype "bidirectional"))
      (node (ref "R1") (pin "1") (pinfunction "1_1") (pintype "passive"))
    )
    (net (code "90") (name "Net-(MCP23017_2-GPB1)") (class "Default")
      (node (ref "MCP23017_2") (pin "2") (pinfunction "GPB1_2") (pintype "bidirectional"))
      (node (ref "R2") (pin "1") (pinfunction "1_1") (pintype "passive"))
    )
    (net (code "91") (name "Net-(MCP23017_2-GPB2)") (class "Default")
      (node (ref "MCP23017_2") (pin "3") (pinfunction "GPB2_3") (pintype "bidirectional"))
      (node (ref "R3") (pin "1") (pinfunction "1_1") (pintype "passive"))
    )
    (net (code "92") (name "Net-(MCP23017_2-GPB7)") (class "Default")
      (node (ref "MCP23017_2") (pin "8") (pinfunction "GPB7_8") (pintype "bidirectional"))
      (node (ref "R12") (pin "1") (pinfunction "1_1") (pintype "passive"))
    )
    (net (code "93") (name "Net-(MCP23017_2-~{RESET})") (class "Default")
      (node (ref "MCP23017_2") (pin "18") (pinfunction "~{RESET}_18") (pintype "input"))
      (node (ref "R34") (pin "2") (pinfunction "2_2") (pintype "passive"))
    )
    (net (code "94") (name "unconnected-(ADX345--1-PadA1)") (class "Default")
      (node (ref "ADX345") (pin "A1") (pinfunction "-1_A1") (pintype "passive"))
    )
    (net (code "95") (name "unconnected-(ADX345--2-PadA2)") (class "Default")
      (node (ref "ADX345") (pin "A2") (pinfunction "-2_A2") (pintype "passive"))
    )
    (net (code "96") (name "unconnected-(ADX345--3-PadA3)") (class "Default")
      (node (ref "ADX345") (pin "A3") (pinfunction "-3_A3") (pintype "passive"))
    )
    (net (code "97") (name "unconnected-(ADX345--4-PadA4)") (class "Default")
      (node (ref "ADX345") (pin "A4") (pinfunction "-4_A4") (pintype "passive"))
    )
    (net (code "98") (name "unconnected-(FRISCHWASSERTANK--1-PadA1)") (class "Default")
      (node (ref "FRISCHWASSERTANK") (pin "A1") (pinfunction "-1_A1") (pintype "passive"))
    )
    (net (code "99") (name "unconnected-(FRISCHWASSERTANK--2-PadA2)") (class "Default")
      (node (ref "FRISCHWASSERTANK") (pin "A2") (pinfunction "-2_A2") (pintype "passive"))
    )
    (net (code "100") (name "unconnected-(FRISCHWASSERTANK--3-PadA3)") (class "Default")
      (node (ref "FRISCHWASSERTANK") (pin "A3") (pinfunction "-3_A3") (pintype "passive"))
    )
    (net (code "101") (name "unconnected-(FRISCHWASSERTANK--4-PadA4)") (class "Default")
      (node (ref "FRISCHWASSERTANK") (pin "A4") (pinfunction "-4_A4") (pintype "passive"))
    )
    (net (code "102") (name "unconnected-(FRISCHWASSERTANK--5-PadA5)") (class "Default")
      (node (ref "FRISCHWASSERTANK") (pin "A5") (pinfunction "-5_A5") (pintype "passive"))
    )
    (net (code "103") (name "unconnected-(FRISCHWASSERTANK--6-PadA6)") (class "Default")
      (node (ref "FRISCHWASSERTANK") (pin "A6") (pinfunction "-6_A6") (pintype "passive"))
    )
    (net (code "104") (name "unconnected-(FRISCHWASSERTANK--7-PadA7)") (class "Default")
      (node (ref "FRISCHWASSERTANK") (pin "A7") (pinfunction "-7_A7") (pintype "passive"))
    )
    (net (code "105") (name "unconnected-(FRISCHWASSERTANK--8-PadA8)") (class "Default")
      (node (ref "FRISCHWASSERTANK") (pin "A8") (pinfunction "-8_A8") (pintype "passive"))
    )
    (net (code "106") (name "unconnected-(FÄKALIENTANK--1-PadA1)") (class "Default")
      (node (ref "FÄKALIENTANK") (pin "A1") (pinfunction "-1_A1") (pintype "passive"))
    )
    (net (code "107") (name "unconnected-(FÄKALIENTANK--2-PadA2)") (class "Default")
      (node (ref "FÄKALIENTANK") (pin "A2") (pinfunction "-2_A2") (pintype "passive"))
    )
    (net (code "108") (name "unconnected-(FÄKALIENTANK--3-PadA3)") (class "Default")
      (node (ref "FÄKALIENTANK") (pin "A3") (pinfunction "-3_A3") (pintype "passive"))
    )
    (net (code "109") (name "unconnected-(FÄKALIENTANK--4-PadA4)") (class "Default")
      (node (ref "FÄKALIENTANK") (pin "A4") (pinfunction "-4_A4") (pintype "passive"))
    )
    (net (code "110") (name "unconnected-(FÄKALIENTANK--5-PadA5)") (class "Default")
      (node (ref "FÄKALIENTANK") (pin "A5") (pinfunction "-5_A5") (pintype "passive"))
    )
    (net (code "111") (name "unconnected-(FÄKALIENTANK--6-PadA6)") (class "Default")
      (node (ref "FÄKALIENTANK") (pin "A6") (pinfunction "-6_A6") (pintype "passive"))
    )
    (net (code "112") (name "unconnected-(FÄKALIENTANK--7-PadA7)") (class "Default")
      (node (ref "FÄKALIENTANK") (pin "A7") (pinfunction "-7_A7") (pintype "passive"))
    )
    (net (code "113") (name "unconnected-(FÄKALIENTANK--8-PadA8)") (class "Default")
      (node (ref "FÄKALIENTANK") (pin "A8") (pinfunction "-8_A8") (pintype "passive"))
    )
    (net (code "114") (name "unconnected-(FÄKALIENTANK-B-7-PadB7)") (class "Default")
      (node (ref "FÄKALIENTANK") (pin "B7") (pinfunction "B-7_B7") (pintype "passive"))
    )
    (net (code "115") (name "unconnected-(FÄKALIENTANK-B-8-PadB8)") (class "Default")
      (node (ref "FÄKALIENTANK") (pin "B8") (pinfunction "B-8_B8") (pintype "passive"))
    )
    (net (code "116") (name "unconnected-(GASWAAGE--1-PadA1)") (class "Default")
      (node (ref "GASWAAGE") (pin "A1") (pinfunction "-1_A1") (pintype "passive"))
    )
    (net (code "117") (name "unconnected-(GASWAAGE--2-PadA2)") (class "Default")
      (node (ref "GASWAAGE") (pin "A2") (pinfunction "-2_A2") (pintype "passive"))
    )
    (net (code "118") (name "unconnected-(GASWAAGE--3-PadA3)") (class "Default")
      (node (ref "GASWAAGE") (pin "A3") (pinfunction "-3_A3") (pintype "passive"))
    )
    (net (code "119") (name "unconnected-(GASWAAGE--4-PadA4)") (class "Default")
      (node (ref "GASWAAGE") (pin "A4") (pinfunction "-4_A4") (pintype "passive"))
    )
    (net (code "120") (name "unconnected-(GEHÄUSEDECKEL-Pad4)") (class "Default")
      (node (ref "GEHÄUSEDECKEL") (pin "4") (pinfunction "4_4") (pintype "passive"))
    )
    (net (code "121") (name "unconnected-(GEHÄUSEDECKEL-Pad6)") (class "Default")
      (node (ref "GEHÄUSEDECKEL") (pin "6") (pinfunction "6_6") (pintype "passive"))
    )
    (net (code "122") (name "unconnected-(GEHÄUSEDECKEL-Pad8)") (class "Default")
      (node (ref "GEHÄUSEDECKEL") (pin "8") (pinfunction "8_8") (pintype "passive"))
    )
    (net (code "123") (name "unconnected-(GEHÄUSEDECKEL-Pad10)") (class "Default")
      (node (ref "GEHÄUSEDECKEL") (pin "10") (pinfunction "10_10") (pintype "passive"))
    )
    (net (code "124") (name "unconnected-(GEHÄUSEDECKEL-Pad12)") (class "Default")
      (node (ref "GEHÄUSEDECKEL") (pin "12") (pinfunction "12_12") (pintype "passive"))
    )
    (net (code "125") (name "unconnected-(GPIO_EXTENSION--1-PadA1)") (class "Default")
      (node (ref "GPIO_EXTENSION") (pin "A1") (pinfunction "-1_A1") (pintype "passive"))
    )
    (net (code "126") (name "unconnected-(GPIO_EXTENSION--2-PadA2)") (class "Default")
      (node (ref "GPIO_EXTENSION") (pin "A2") (pinfunction "-2_A2") (pintype "passive"))
    )
    (net (code "127") (name "unconnected-(GPIO_EXTENSION--3-PadA3)") (class "Default")
      (node (ref "GPIO_EXTENSION") (pin "A3") (pinfunction "-3_A3") (pintype "passive"))
    )
    (net (code "128") (name "unconnected-(GPIO_EXTENSION--4-PadA4)") (class "Default")
      (node (ref "GPIO_EXTENSION") (pin "A4") (pinfunction "-4_A4") (pintype "passive"))
    )
    (net (code "129") (name "unconnected-(GPIO_EXTENSION--5-PadA5)") (class "Default")
      (node (ref "GPIO_EXTENSION") (pin "A5") (pinfunction "-5_A5") (pintype "passive"))
    )
    (net (code "130") (name "unconnected-(GPIO_EXTENSION--6-PadA6)") (class "Default")
      (node (ref "GPIO_EXTENSION") (pin "A6") (pinfunction "-6_A6") (pintype "passive"))
    )
    (net (code "131") (name "unconnected-(GPIO_EXTENSION--7-PadA7)") (class "Default")
      (node (ref "GPIO_EXTENSION") (pin "A7") (pinfunction "-7_A7") (pintype "passive"))
    )
    (net (code "132") (name "unconnected-(GPIO_EXTENSION--8-PadA8)") (class "Default")
      (node (ref "GPIO_EXTENSION") (pin "A8") (pinfunction "-8_A8") (pintype "passive"))
    )
    (net (code "133") (name "unconnected-(GPIO_EXTENSION--9-PadA9)") (class "Default")
      (node (ref "GPIO_EXTENSION") (pin "A9") (pinfunction "-9_A9") (pintype "passive"))
    )
    (net (code "134") (name "unconnected-(GPIO_EXTENSION--10-PadA10)") (class "Default")
      (node (ref "GPIO_EXTENSION") (pin "A10") (pinfunction "-10_A10") (pintype "passive"))
    )
    (net (code "135") (name "unconnected-(GPIO_EXTENSION--11-PadA11)") (class "Default")
      (node (ref "GPIO_EXTENSION") (pin "A11") (pinfunction "-11_A11") (pintype "passive"))
    )
    (net (code "136") (name "unconnected-(GPIO_EXTENSION--12-PadA12)") (class "Default")
      (node (ref "GPIO_EXTENSION") (pin "A12") (pinfunction "-12_A12") (pintype "passive"))
    )
    (net (code "137") (name "unconnected-(GPIO_EXTENSION--13-PadA13)") (class "Default")
      (node (ref "GPIO_EXTENSION") (pin "A13") (pinfunction "-13_A13") (pintype "passive"))
    )
    (net (code "138") (name "unconnected-(GPIO_EXTENSION--14-PadA14)") (class "Default")
      (node (ref "GPIO_EXTENSION") (pin "A14") (pinfunction "-14_A14") (pintype "passive"))
    )
    (net (code "139") (name "unconnected-(GPIO_EXTENSION--15-PadA15)") (class "Default")
      (node (ref "GPIO_EXTENSION") (pin "A15") (pinfunction "-15_A15") (pintype "passive"))
    )
    (net (code "140") (name "unconnected-(GPIO_EXTENSION--16-PadA16)") (class "Default")
      (node (ref "GPIO_EXTENSION") (pin "A16") (pinfunction "-16_A16") (pintype "passive"))
    )
    (net (code "141") (name "unconnected-(HX711-EXTERN--1-PadA1)") (class "Default")
      (node (ref "HX711-EXTERN") (pin "A1") (pinfunction "-1_A1") (pintype "passive"))
    )
    (net (code "142") (name "unconnected-(HX711-EXTERN--2-PadA2)") (class "Default")
      (node (ref "HX711-EXTERN") (pin "A2") (pinfunction "-2_A2") (pintype "passive"))
    )
    (net (code "143") (name "unconnected-(HX711-EXTERN--3-PadA3)") (class "Default")
      (node (ref "HX711-EXTERN") (pin "A3") (pinfunction "-3_A3") (pintype "passive"))
    )
    (net (code "144") (name "unconnected-(HX711-EXTERN--4-PadA4)") (class "Default")
      (node (ref "HX711-EXTERN") (pin "A4") (pinfunction "-4_A4") (pintype "passive"))
    )
    (net (code "145") (name "unconnected-(HX711-PadB+)") (class "Default")
      (node (ref "HX711") (pin "B+") (pinfunction "B+_B+") (pintype "bidirectional"))
    )
    (net (code "146") (name "unconnected-(HX711-PadB-)") (class "Default")
      (node (ref "HX711") (pin "B-") (pinfunction "B-_B-") (pintype "bidirectional"))
    )
    (net (code "147") (name "unconnected-(I2C-EXTENSION-Pad2)") (class "Default")
      (node (ref "I2C-EXTENSION") (pin "2") (pinfunction "2_2") (pintype "passive"))
    )
    (net (code "148") (name "unconnected-(I2C-EXTENSION-Pad4)") (class "Default")
      (node (ref "I2C-EXTENSION") (pin "4") (pinfunction "4_4") (pintype "passive"))
    )
    (net (code "149") (name "unconnected-(I2C-EXTENSION-Pad6)") (class "Default")
      (node (ref "I2C-EXTENSION") (pin "6") (pinfunction "6_6") (pintype "passive"))
    )
    (net (code "150") (name "unconnected-(I2C-EXTENSION-Pad7)") (class "Default")
      (node (ref "I2C-EXTENSION") (pin "7") (pinfunction "7_7") (pintype "passive"))
    )
    (net (code "151") (name "unconnected-(I2C-EXTENSION-Pad8)") (class "Default")
      (node (ref "I2C-EXTENSION") (pin "8") (pinfunction "8_8") (pintype "passive"))
    )
    (net (code "152") (name "unconnected-(I2EXT1-N.C.-Pad5)") (class "Default")
      (node (ref "I2EXT1") (pin "5") (pinfunction "N.C._5") (pintype "no_connect"))
    )
    (net (code "153") (name "unconnected-(I2EXT1-N.C._2-Pad1)") (class "Default")
      (node (ref "I2EXT1") (pin "1") (pinfunction "N.C._2_1") (pintype "no_connect"))
    )
    (net (code "154") (name "unconnected-(I2EXT2-N.C.-Pad5)") (class "Default")
      (node (ref "I2EXT2") (pin "5") (pinfunction "N.C._5") (pintype "no_connect"))
    )
    (net (code "155") (name "unconnected-(I2EXT2-N.C._2-Pad1)") (class "Default")
      (node (ref "I2EXT2") (pin "1") (pinfunction "N.C._2_1") (pintype "no_connect"))
    )
    (net (code "156") (name "unconnected-(KLIMA1--1-PadA1)") (class "Default")
      (node (ref "KLIMA1") (pin "A1") (pinfunction "-1_A1") (pintype "passive"))
    )
    (net (code "157") (name "unconnected-(KLIMA1--2-PadA2)") (class "Default")
      (node (ref "KLIMA1") (pin "A2") (pinfunction "-2_A2") (pintype "passive"))
    )
    (net (code "158") (name "unconnected-(KLIMA1--3-PadA3)") (class "Default")
      (node (ref "KLIMA1") (pin "A3") (pinfunction "-3_A3") (pintype "passive"))
    )
    (net (code "159") (name "unconnected-(KLIMA1--4-PadA4)") (class "Default")
      (node (ref "KLIMA1") (pin "A4") (pinfunction "-4_A4") (pintype "passive"))
    )
    (net (code "160") (name "unconnected-(KLIMA2--1-PadA1)") (class "Default")
      (node (ref "KLIMA2") (pin "A1") (pinfunction "-1_A1") (pintype "passive"))
    )
    (net (code "161") (name "unconnected-(KLIMA2--2-PadA2)") (class "Default")
      (node (ref "KLIMA2") (pin "A2") (pinfunction "-2_A2") (pintype "passive"))
    )
    (net (code "162") (name "unconnected-(KLIMA2--3-PadA3)") (class "Default")
      (node (ref "KLIMA2") (pin "A3") (pinfunction "-3_A3") (pintype "passive"))
    )
    (net (code "163") (name "unconnected-(KLIMA2--4-PadA4)") (class "Default")
      (node (ref "KLIMA2") (pin "A4") (pinfunction "-4_A4") (pintype "passive"))
    )
    (net (code "164") (name "unconnected-(KüHLSCHR.--1-PadA1)") (class "Default")
      (node (ref "KüHLSCHR.") (pin "A1") (pinfunction "-1_A1") (pintype "passive"))
    )
    (net (code "165") (name "unconnected-(KüHLSCHR.--2-PadA2)") (class "Default")
      (node (ref "KüHLSCHR.") (pin "A2") (pinfunction "-2_A2") (pintype "passive"))
    )
    (net (code "166") (name "unconnected-(KüHLSCHR.--3-PadA3)") (class "Default")
      (node (ref "KüHLSCHR.") (pin "A3") (pinfunction "-3_A3") (pintype "passive"))
    )
    (net (code "167") (name "unconnected-(LED-HL--1-PadA1)") (class "Default")
      (node (ref "LED-HL") (pin "A1") (pinfunction "-1_A1") (pintype "passive"))
    )
    (net (code "168") (name "unconnected-(LED-HL--2-PadA2)") (class "Default")
      (node (ref "LED-HL") (pin "A2") (pinfunction "-2_A2") (pintype "passive"))
    )
    (net (code "169") (name "unconnected-(LED-HL--3-PadA3)") (class "Default")
      (node (ref "LED-HL") (pin "A3") (pinfunction "-3_A3") (pintype "passive"))
    )
    (net (code "170") (name "unconnected-(LED-HL--4-PadA4)") (class "Default")
      (node (ref "LED-HL") (pin "A4") (pinfunction "-4_A4") (pintype "passive"))
    )
    (net (code "171") (name "unconnected-(LED-HR--1-PadA1)") (class "Default")
      (node (ref "LED-HR") (pin "A1") (pinfunction "-1_A1") (pintype "passive"))
    )
    (net (code "172") (name "unconnected-(LED-HR--2-PadA2)") (class "Default")
      (node (ref "LED-HR") (pin "A2") (pinfunction "-2_A2") (pintype "passive"))
    )
    (net (code "173") (name "unconnected-(LED-HR--3-PadA3)") (class "Default")
      (node (ref "LED-HR") (pin "A3") (pinfunction "-3_A3") (pintype "passive"))
    )
    (net (code "174") (name "unconnected-(LED-HR--4-PadA4)") (class "Default")
      (node (ref "LED-HR") (pin "A4") (pinfunction "-4_A4") (pintype "passive"))
    )
    (net (code "175") (name "unconnected-(LED-VD--1-PadA1)") (class "Default")
      (node (ref "LED-VD") (pin "A1") (pinfunction "-1_A1") (pintype "passive"))
    )
    (net (code "176") (name "unconnected-(LED-VD--2-PadA2)") (class "Default")
      (node (ref "LED-VD") (pin "A2") (pinfunction "-2_A2") (pintype "passive"))
    )
    (net (code "177") (name "unconnected-(LED-VD--3-PadA3)") (class "Default")
      (node (ref "LED-VD") (pin "A3") (pinfunction "-3_A3") (pintype "passive"))
    )
    (net (code "178") (name "unconnected-(LED-VD--4-PadA4)") (class "Default")
      (node (ref "LED-VD") (pin "A4") (pinfunction "-4_A4") (pintype "passive"))
    )
    (net (code "179") (name "unconnected-(LED-VL--1-PadA1)") (class "Default")
      (node (ref "LED-VL") (pin "A1") (pinfunction "-1_A1") (pintype "passive"))
    )
    (net (code "180") (name "unconnected-(LED-VL--2-PadA2)") (class "Default")
      (node (ref "LED-VL") (pin "A2") (pinfunction "-2_A2") (pintype "passive"))
    )
    (net (code "181") (name "unconnected-(LED-VL--3-PadA3)") (class "Default")
      (node (ref "LED-VL") (pin "A3") (pinfunction "-3_A3") (pintype "passive"))
    )
    (net (code "182") (name "unconnected-(LED-VL--4-PadA4)") (class "Default")
      (node (ref "LED-VL") (pin "A4") (pinfunction "-4_A4") (pintype "passive"))
    )
    (net (code "183") (name "unconnected-(LED-VR--1-PadA1)") (class "Default")
      (node (ref "LED-VR") (pin "A1") (pinfunction "-1_A1") (pintype "passive"))
    )
    (net (code "184") (name "unconnected-(LED-VR--2-PadA2)") (class "Default")
      (node (ref "LED-VR") (pin "A2") (pinfunction "-2_A2") (pintype "passive"))
    )
    (net (code "185") (name "unconnected-(LED-VR--3-PadA3)") (class "Default")
      (node (ref "LED-VR") (pin "A3") (pinfunction "-3_A3") (pintype "passive"))
    )
    (net (code "186") (name "unconnected-(LED-VR--4-PadA4)") (class "Default")
      (node (ref "LED-VR") (pin "A4") (pinfunction "-4_A4") (pintype "passive"))
    )
    (net (code "187") (name "unconnected-(LED-ZL--1-PadA1)") (class "Default")
      (node (ref "LED-ZL") (pin "A1") (pinfunction "-1_A1") (pintype "passive"))
    )
    (net (code "188") (name "unconnected-(LED-ZL--2-PadA2)") (class "Default")
      (node (ref "LED-ZL") (pin "A2") (pinfunction "-2_A2") (pintype "passive"))
    )
    (net (code "189") (name "unconnected-(LED-ZL--3-PadA3)") (class "Default")
      (node (ref "LED-ZL") (pin "A3") (pinfunction "-3_A3") (pintype "passive"))
    )
    (net (code "190") (name "unconnected-(LED-ZL--4-PadA4)") (class "Default")
      (node (ref "LED-ZL") (pin "A4") (pinfunction "-4_A4") (pintype "passive"))
    )
    (net (code "191") (name "unconnected-(LED-ZR--1-PadA1)") (class "Default")
      (node (ref "LED-ZR") (pin "A1") (pinfunction "-1_A1") (pintype "passive"))
    )
    (net (code "192") (name "unconnected-(LED-ZR--2-PadA2)") (class "Default")
      (node (ref "LED-ZR") (pin "A2") (pinfunction "-2_A2") (pintype "passive"))
    )
    (net (code "193") (name "unconnected-(LED-ZR--3-PadA3)") (class "Default")
      (node (ref "LED-ZR") (pin "A3") (pinfunction "-3_A3") (pintype "passive"))
    )
    (net (code "194") (name "unconnected-(LED-ZR--4-PadA4)") (class "Default")
      (node (ref "LED-ZR") (pin "A4") (pinfunction "-4_A4") (pintype "passive"))
    )
    (net (code "195") (name "unconnected-(MCP23017_1-INTA-Pad20)") (class "Default")
      (node (ref "MCP23017_1") (pin "20") (pinfunction "INTA_20") (pintype "output"))
    )
    (net (code "196") (name "unconnected-(MCP23017_1-INTB-Pad19)") (class "Default")
      (node (ref "MCP23017_1") (pin "19") (pinfunction "INTB_19") (pintype "output"))
    )
    (net (code "197") (name "unconnected-(MCP23017_2-INTA-Pad20)") (class "Default")
      (node (ref "MCP23017_2") (pin "20") (pinfunction "INTA_20") (pintype "output"))
    )
    (net (code "198") (name "unconnected-(MCP23017_2-INTB-Pad19)") (class "Default")
      (node (ref "MCP23017_2") (pin "19") (pinfunction "INTB_19") (pintype "output"))
    )
    (net (code "199") (name "unconnected-(RADAR--1-PadA1)") (class "Default")
      (node (ref "RADAR") (pin "A1") (pinfunction "-1_A1") (pintype "passive"))
    )
    (net (code "200") (name "unconnected-(RADAR--2-PadA2)") (class "Default")
      (node (ref "RADAR") (pin "A2") (pinfunction "-2_A2") (pintype "passive"))
    )
    (net (code "201") (name "unconnected-(RADAR--3-PadA3)") (class "Default")
      (node (ref "RADAR") (pin "A3") (pinfunction "-3_A3") (pintype "passive"))
    )
    (net (code "202") (name "unconnected-(RASPBERRY-PI-Pad10)") (class "Default")
      (node (ref "RASPBERRY-PI") (pin "10") (pinfunction "10_10") (pintype "passive"))
    )
  )
)
